# Sheet1.net
KiCad netlist of a schematic drawn in Altium Designer
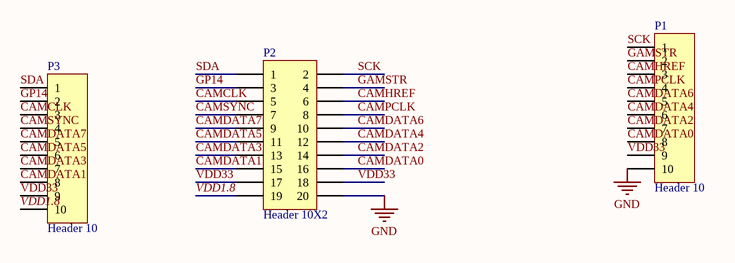
[diagram p0: Sheet1.SchDoc]

(export (version "E")
  (design (tool "Eeschema 10.0.6"))
  (components
    (comp (ref "P1")
      (value "Header 10")
      (footprint "HDR1X10")
      (description "Header, 10-Pin")
      (fields (field (name "PUBLISHER") "Altium Limited"))
      (libsource (lib "Miscellaneous Connectors") (part "Header 10"))
    )
    (comp (ref "P2")
      (value "Header 10X2")
      (footprint "H20X1 2.0")
      (description "Header, 10-Pin, Dual row")
      (fields (field (name "PUBLISHER") "Altium Limited"))
      (libsource (lib "Miscellaneous Connectors") (part "Header 10X2"))
    )
    (comp (ref "P3")
      (value "Header 10")
      (footprint "HDR1X10")
      (description "Header, 10-Pin")
      (fields (field (name "PUBLISHER") "Altium Limited"))
      (libsource (lib "Miscellaneous Connectors") (part "Header 10"))
    )
  )
  (nets
    (net (code "1") (name "/CAMCLK") (class "Default")
      (node (ref "P2") (pin "5") (pinfunction "5_5") (pintype "passive"))
      (node (ref "P3") (pin "3") (pinfunction "3_3") (pintype "passive"))
    )
    (net (code "2") (name "/CAMDATA0") (class "Default")
      (node (ref "P1") (pin "8") (pinfunction "8_8") (pintype "passive"))
      (node (ref "P2") (pin "16") (pinfunction "16_16") (pintype "passive"))
    )
    (net (code "3") (name "/CAMDATA1") (class "Default")
      (node (ref "P2") (pin "15") (pinfunction "15_15") (pintype "passive"))
      (node (ref "P3") (pin "8") (pinfunction "8_8") (pintype "passive"))
    )
    (net (code "4") (name "/CAMDATA2") (class "Default")
      (node (ref "P1") (pin "7") (pinfunction "7_7") (pintype "passive"))
      (node (ref "P2") (pin "14") (pinfunction "14_14") (pintype "passive"))
    )
    (net (code "5") (name "/CAMDATA3") (class "Default")
      (node (ref "P2") (pin "13") (pinfunction "13_13") (pintype "passive"))
      (node (ref "P3") (pin "7") (pinfunction "7_7") (pintype "passive"))
    )
    (net (code "6") (name "/CAMDATA4") (class "Default")
      (node (ref "P1") (pin "6") (pinfunction "6_6") (pintype "passive"))
      (node (ref "P2") (pin "12") (pinfunction "12_12") (pintype "passive"))
    )
    (net (code "7") (name "/CAMDATA5") (class "Default")
      (node (ref "P2") (pin "11") (pinfunction "11_11") (pintype "passive"))
      (node (ref "P3") (pin "6") (pinfunction "6_6") (pintype "passive"))
    )
    (net (code "8") (name "/CAMDATA6") (class "Default")
      (node (ref "P1") (pin "5") (pinfunction "5_5") (pintype "passive"))
      (node (ref "P2") (pin "10") (pinfunction "10_10") (pintype "passive"))
    )
    (net (code "9") (name "/CAMDATA7") (class "Default")
      (node (ref "P2") (pin "9") (pinfunction "9_9") (pintype "passive"))
      (node (ref "P3") (pin "5") (pinfunction "5_5") (pintype "passive"))
    )
    (net (code "10") (name "/CAMHREF") (class "Default")
      (node (ref "P1") (pin "3") (pinfunction "3_3") (pintype "passive"))
      (node (ref "P2") (pin "6") (pinfunction "6_6") (pintype "passive"))
    )
    (net (code "11") (name "/CAMPCLK") (class "Default")
      (node (ref "P1") (pin "4") (pinfunction "4_4") (pintype "passive"))
      (node (ref "P2") (pin "8") (pinfunction "8_8") (pintype "passive"))
    )
    (net (code "12") (name "/CAMSYNC") (class "Default")
      (node (ref "P2") (pin "7") (pinfunction "7_7") (pintype "passive"))
      (node (ref "P3") (pin "4") (pinfunction "4_4") (pintype "passive"))
    )
    (net (code "13") (name "/GAMSTR") (class "Default")
      (node (ref "P1") (pin "2") (pinfunction "2_2") (pintype "passive"))
      (node (ref "P2") (pin "4") (pinfunction "4_4") (pintype "passive"))
    )
    (net (code "14") (name "/GP14") (class "Default")
      (node (ref "P2") (pin "3") (pinfunction "3_3") (pintype "passive"))
      (node (ref "P3") (pin "2") (pinfunction "2_2") (pintype "passive"))
    )
    (net (code "15") (name "/SCK") (class "Default")
      (node (ref "P1") (pin "1") (pinfunction "1_1") (pintype "passive"))
      (node (ref "P2") (pin "2") (pinfunction "2_2") (pintype "passive"))
    )
    (net (code "16") (name "/SDA") (class "Default")
      (node (ref "P2") (pin "1") (pinfunction "1_1") (pintype "passive"))
      (node (ref "P3") (pin "1") (pinfunction "1_1") (pintype "passive"))
    )
    (net (code "17") (name "/VDD1.8") (class "Default")
      (node (ref "P2") (pin "19") (pinfunction "19_19") (pintype "passive"))
      (node (ref "P3") (pin "10") (pinfunction "10_10") (pintype "passive"))
    )
    (net (code "18") (name "/VDD33") (class "Default")
      (node (ref "P1") (pin "9") (pinfunction "9_9") (pintype "passive"))
      (node (ref "P2") (pin "17") (pinfunction "17_17") (pintype "passive"))
      (node (ref "P2") (pin "18") (pinfunction "18_18") (pintype "passive"))
      (node (ref "P3") (pin "9") (pinfunction "9_9") (pintype "passive"))
    )
    (net (code "19") (name "GND") (class "Default")
      (node (ref "P1") (pin "10") (pinfunction "10_10") (pintype "passive"))
      (node (ref "P2") (pin "20") (pinfunction "20_20") (pintype "passive"))
    )
  )
)
